# MCU_tiva.net
KiCad netlist of a schematic drawn in Altium Designer
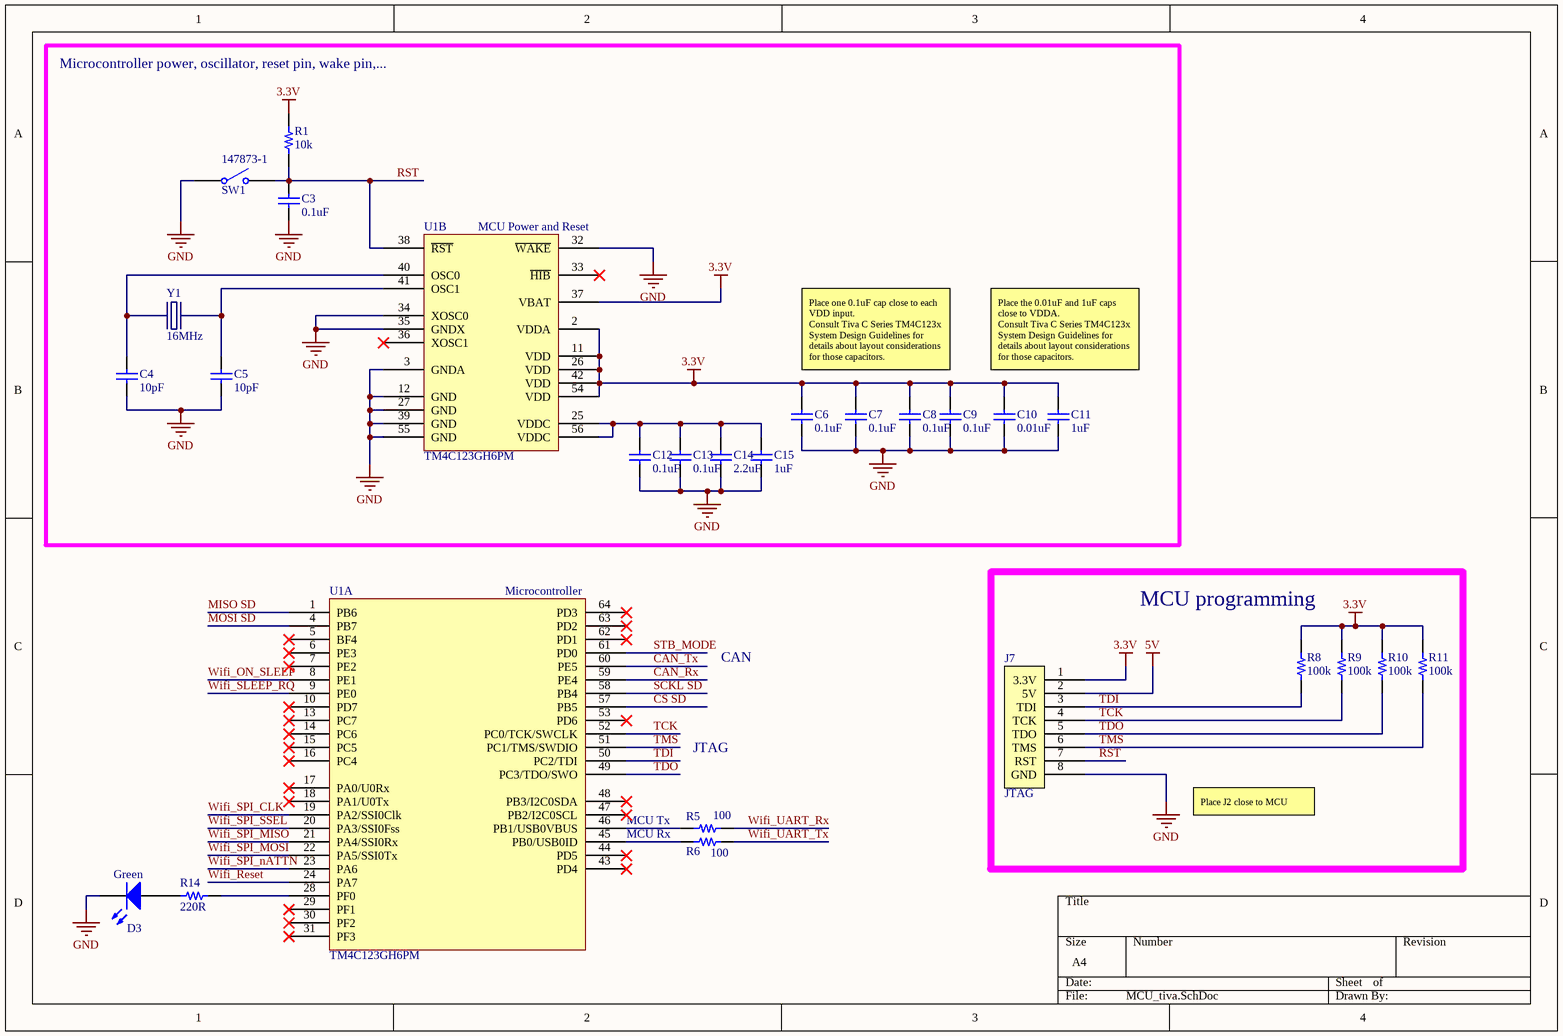
[diagram p0: MCU_tiva.SchDoc]

(export (version "E")
  (design (tool "Eeschema 10.0.6"))
  (components
    (comp (ref "C3")
      (value "0.1uF")
      (footprint "Capacitors:C0603")
      (description "0.1uF ceramic capacitor")
      (fields (field (name "MANUFACTURER") "TDK Corporation") (field (name "TOLERANCE") "10%"))
      (libsource (lib "Capacitors") (part "CAP CER 0603 0.1uF 50V C0G 10%"))
    )
    (comp (ref "C4")
      (value "10pF")
      (footprint "Capacitors:C0603")
      (description "10pF ceramic capacitor")
      (fields (field (name "MANUFACTURER") "TDK Corporation") (field (name "TOLERANCE") "5%"))
      (libsource (lib "Capacitors") (part "CAP CER 0603 10pF 50V C0G 5%"))
    )
    (comp (ref "C5")
      (value "10pF")
      (footprint "Capacitors:C0603")
      (description "10pF ceramic capacitor")
      (fields (field (name "MANUFACTURER") "TDK Corporation") (field (name "TOLERANCE") "5%"))
      (libsource (lib "Capacitors") (part "CAP CER 0603 10pF 50V C0G 5%"))
    )
    (comp (ref "C6")
      (value "0.1uF")
      (footprint "Capacitors:C0603")
      (description "0.1uF ceramic capacitor")
      (fields (field (name "MANUFACTURER") "TDK Corporation") (field (name "TOLERANCE") "10%"))
      (libsource (lib "Capacitors") (part "CAP CER 0603 0.1uF 50V C0G 10%"))
    )
    (comp (ref "C7")
      (value "0.1uF")
      (footprint "Capacitors:C0603")
      (description "0.1uF ceramic capacitor")
      (fields (field (name "MANUFACTURER") "TDK Corporation") (field (name "TOLERANCE") "10%"))
      (libsource (lib "Capacitors") (part "CAP CER 0603 0.1uF 50V C0G 10%"))
    )
    (comp (ref "C8")
      (value "0.1uF")
      (footprint "Capacitors:C0603")
      (description "0.1uF ceramic capacitor")
      (fields (field (name "MANUFACTURER") "TDK Corporation") (field (name "TOLERANCE") "10%"))
      (libsource (lib "Capacitors") (part "CAP CER 0603 0.1uF 50V C0G 10%"))
    )
    (comp (ref "C9")
      (value "0.1uF")
      (footprint "Capacitors:C0603")
      (description "0.1uF ceramic capacitor")
      (fields (field (name "MANUFACTURER") "TDK Corporation") (field (name "TOLERANCE") "10%"))
      (libsource (lib "Capacitors") (part "CAP CER 0603 0.1uF 50V C0G 10%"))
    )
    (comp (ref "C10")
      (value "0.01uF")
      (footprint "Capacitors:C0603")
      (description "0.01uF ceramic capacitor")
      (fields (field (name "MANUFACTURER") "TDK Corporation") (field (name "TOLERANCE") "10%"))
      (libsource (lib "Capacitors") (part "CAP CER 0603 0.01uF 50V X7R 10%"))
    )
    (comp (ref "C11")
      (value "1uF")
      (footprint "Capacitors:C0603")
      (description "1uF ceramic capacitor")
      (fields (field (name "MANUFACTURER") "TDK Corporation") (field (name "TOLERANCE") "20%"))
      (libsource (lib "Capacitors") (part "CAP CER 0603 1uF 25V X7R 20%"))
    )
    (comp (ref "C12")
      (value "0.1uF")
      (footprint "Capacitors:C0603")
      (description "0.1uF ceramic capacitor")
      (fields (field (name "MANUFACTURER") "TDK Corporation") (field (name "TOLERANCE") "10%"))
      (libsource (lib "Capacitors") (part "CAP CER 0603 0.1uF 50V C0G 10%"))
    )
    (comp (ref "C13")
      (value "0.1uF")
      (footprint "Capacitors:C0603")
      (description "0.1uF ceramic capacitor")
      (fields (field (name "MANUFACTURER") "TDK Corporation") (field (name "TOLERANCE") "10%"))
      (libsource (lib "Capacitors") (part "CAP CER 0603 0.1uF 50V C0G 10%"))
    )
    (comp (ref "C14")
      (value "2.2uF")
      (footprint "Capacitors:C0603")
      (description "2.2uF ceramic capacitor")
      (fields (field (name "MANUFACTURER") "TDK Corporation") (field (name "TOLERANCE") "10%"))
      (libsource (lib "Capacitors") (part "CAP CER 0603 2.2uF 6.3V X7R 10%"))
    )
    (comp (ref "C15")
      (value "1uF")
      (footprint "Capacitors:C0603")
      (description "1uF ceramic capacitor")
      (fields (field (name "MANUFACTURER") "TDK Corporation") (field (name "TOLERANCE") "20%"))
      (libsource (lib "Capacitors") (part "CAP CER 0603 1uF 25V X7R 20%"))
    )
    (comp (ref "D3")
      (value "Green")
      (footprint "Diodes:LED1206")
      (description "Green LED 1206")
      (fields (field (name "PART_NUMBER") "LTST-C150KGKT") (field (name "MANUFACTURER") "Liteon"))
      (libsource (lib "Diodes") (part "LTST-C150KGKT"))
    )
    (comp (ref "J7")
      (value "JTAG")
      (footprint "Connectors:JTAG_Header")
      (description "JTAG header, MCU programming")
      (libsource (lib "Connectors") (part "JTAG_Header"))
    )
    (comp (ref "R1")
      (value "10k")
      (footprint "Resistors:R0603")
      (description "10 kOhms resistor")
      (fields (field (name "PART_NUMBER") "CRCW060310K0JNEA") (field (name "MANUFACTURER") "Vishay"))
      (libsource (lib "Resistors") (part "RES 0603 10k 5% 0.1W"))
    )
    (comp (ref "R5")
      (value "100")
      (footprint "Resistors:R0603")
      (description "100 Ohms resistor, 1/4W")
      (fields (field (name "PART_NUMBER") "ESR03EZPJ101") (field (name "MANUFACTURER") "Rohm Semiconductor"))
      (libsource (lib "Resistors") (part "RES 0603 100R 5% 1/4W"))
    )
    (comp (ref "R6")
      (value "100")
      (footprint "Resistors:R0603")
      (description "100 Ohms resistor, 1/4W")
      (fields (field (name "PART_NUMBER") "ESR03EZPJ101") (field (name "MANUFACTURER") "Rohm Semiconductor"))
      (libsource (lib "Resistors") (part "RES 0603 100R 5% 1/4W"))
    )
    (comp (ref "R8")
      (value "100k")
      (footprint "Resistors:R0603")
      (description "100 kOhm resistor")
      (fields (field (name "PART_NUMBER") "CRCW0603100KJNEA") (field (name "MANUFACTURER") "Vishay"))
      (libsource (lib "Resistors") (part "RES 0603 100k 5% 0.1W"))
    )
    (comp (ref "R9")
      (value "100k")
      (footprint "Resistors:R0603")
      (description "100 kOhm resistor")
      (fields (field (name "PART_NUMBER") "CRCW0603100KJNEA") (field (name "MANUFACTURER") "Vishay"))
      (libsource (lib "Resistors") (part "RES 0603 100k 5% 0.1W"))
    )
    (comp (ref "R10")
      (value "100k")
      (footprint "Resistors:R0603")
      (description "100 kOhm resistor")
      (fields (field (name "PART_NUMBER") "CRCW0603100KJNEA") (field (name "MANUFACTURER") "Vishay"))
      (libsource (lib "Resistors") (part "RES 0603 100k 5% 0.1W"))
    )
    (comp (ref "R11")
      (value "100k")
      (footprint "Resistors:R0603")
      (description "100 kOhm resistor")
      (fields (field (name "PART_NUMBER") "CRCW0603100KJNEA") (field (name "MANUFACTURER") "Vishay"))
      (libsource (lib "Resistors") (part "RES 0603 100k 5% 0.1W"))
    )
    (comp (ref "R14")
      (value "220R")
      (footprint "Resistors:R0603")
      (description "220 Ohms resistor, 1/4W")
      (fields (field (name "PART_NUMBER") "ESR03EZPJ221") (field (name "MANUFACTURER") "Rohm Semiconductor"))
      (libsource (lib "Resistors") (part "RES 0603 220R 5% 1/4W"))
    )
    (comp (ref "SW1")
      (value "147873-1")
      (footprint "Other:147873")
      (description "Pushbutton switch SPST, 2 pins")
      (fields (field (name "MANUFACTURER") "TE Connectivity"))
      (libsource (lib "Other") (part "147873-1"))
    )
    (comp (ref "U1")
      (value "Microcontroller")
      (footprint "IC:LQFP64")
      (description "32 bit Microcontroller")
      (fields (field (name "MANUFACTURER") "Texas Instrument") (field (name "PART_NUMBER") "TM4C123GH6PM"))
      (libsource (lib "IC") (part "TM4C123GN6PM"))
    )
    (comp (ref "Y1")
      (value "16MHz")
      (footprint "NX5032GA")
      (description "Crystal Oscillator 16 MHz")
      (fields (field (name "MANUFACTURER") "NDK") (field (name "PART_NUMBER") "NX5032GA-16.000M-LN-CD-1"))
      (libsource (lib "Other") (part "NX5043GA-16.00MHz"))
    )
  )
  (nets
    (net (code "1") (name "/CAN_Rx") (class "Default")
      (node (ref "U1") (pin "59") (pinfunction "PE4_59") (pintype "passive"))
    )
    (net (code "2") (name "/CAN_Tx") (class "Default")
      (node (ref "U1") (pin "60") (pinfunction "PE5_60") (pintype "passive"))
    )
    (net (code "3") (name "/CS SD") (class "Default")
      (node (ref "U1") (pin "57") (pinfunction "PB5_57") (pintype "passive"))
    )
    (net (code "4") (name "/MISO SD") (class "Default")
      (node (ref "U1") (pin "1") (pinfunction "PB6_1") (pintype "passive"))
    )
    (net (code "5") (name "/MOSI SD") (class "Default")
      (node (ref "U1") (pin "4") (pinfunction "PB7_4") (pintype "passive"))
    )
    (net (code "6") (name "/RST") (class "Default")
      (node (ref "C3") (pin "2") (pinfunction "2_2") (pintype "passive"))
      (node (ref "J7") (pin "7") (pinfunction "RST_7") (pintype "passive"))
      (node (ref "R1") (pin "1") (pinfunction "1_1") (pintype "passive"))
      (node (ref "SW1") (pin "2") (pinfunction "NO_2") (pintype "passive"))
      (node (ref "U1") (pin "38") (pinfunction "~{RST}_38") (pintype "passive"))
    )
    (net (code "7") (name "/SCKL SD") (class "Default")
      (node (ref "U1") (pin "58") (pinfunction "PB4_58") (pintype "passive"))
    )
    (net (code "8") (name "/STB_MODE") (class "Default")
      (node (ref "U1") (pin "61") (pinfunction "PD0_61") (pintype "passive"))
    )
    (net (code "9") (name "/TCK") (class "Default")
      (node (ref "J7") (pin "4") (pinfunction "TCK_4") (pintype "passive"))
      (node (ref "R9") (pin "1") (pinfunction "1_1") (pintype "passive"))
      (node (ref "U1") (pin "52") (pinfunction "PC0/TCK/SWCLK_52") (pintype "passive"))
    )
    (net (code "10") (name "/TDI") (class "Default")
      (node (ref "J7") (pin "3") (pinfunction "TDI_3") (pintype "passive"))
      (node (ref "R8") (pin "1") (pinfunction "1_1") (pintype "passive"))
      (node (ref "U1") (pin "50") (pinfunction "PC2/TDI_50") (pintype "passive"))
    )
    (net (code "11") (name "/TDO") (class "Default")
      (node (ref "J7") (pin "5") (pinfunction "TDO_5") (pintype "passive"))
      (node (ref "R10") (pin "1") (pinfunction "1_1") (pintype "passive"))
      (node (ref "U1") (pin "49") (pinfunction "PC3/TDO/SWO_49") (pintype "passive"))
    )
    (net (code "12") (name "/TMS") (class "Default")
      (node (ref "J7") (pin "6") (pinfunction "TMS_6") (pintype "passive"))
      (node (ref "R11") (pin "1") (pinfunction "1_1") (pintype "passive"))
      (node (ref "U1") (pin "51") (pinfunction "PC1/TMS/SWDIO_51") (pintype "passive"))
    )
    (net (code "13") (name "/Wifi_ON_SLEEP") (class "Default")
      (node (ref "U1") (pin "8") (pinfunction "PE1_8") (pintype "passive"))
    )
    (net (code "14") (name "/Wifi_Reset") (class "Default")
      (node (ref "U1") (pin "24") (pinfunction "PA7_24") (pintype "passive"))
    )
    (net (code "15") (name "/Wifi_SLEEP_RQ") (class "Default")
      (node (ref "U1") (pin "9") (pinfunction "PE0_9") (pintype "passive"))
    )
    (net (code "16") (name "/Wifi_SPI_CLK") (class "Default")
      (node (ref "U1") (pin "19") (pinfunction "PA2/SSI0Clk_19") (pintype "passive"))
    )
    (net (code "17") (name "/Wifi_SPI_MISO") (class "Default")
      (node (ref "U1") (pin "21") (pinfunction "PA4/SSI0Rx_21") (pintype "passive"))
    )
    (net (code "18") (name "/Wifi_SPI_MOSI") (class "Default")
      (node (ref "U1") (pin "22") (pinfunction "PA5/SSI0Tx_22") (pintype "passive"))
    )
    (net (code "19") (name "/Wifi_SPI_SSEL") (class "Default")
      (node (ref "U1") (pin "20") (pinfunction "PA3/SSI0Fss_20") (pintype "passive"))
    )
    (net (code "20") (name "/Wifi_SPI_nATTN") (class "Default")
      (node (ref "U1") (pin "23") (pinfunction "PA6_23") (pintype "passive"))
    )
    (net (code "21") (name "/Wifi_UART_Rx") (class "Default")
      (node (ref "R5") (pin "1") (pinfunction "1_1") (pintype "passive"))
    )
    (net (code "22") (name "/Wifi_UART_Tx") (class "Default")
      (node (ref "R6") (pin "1") (pinfunction "1_1") (pintype "passive"))
    )
    (net (code "23") (name "3.3V") (class "Default")
      (node (ref "C10") (pin "2") (pinfunction "2_2") (pintype "passive"))
      (node (ref "C11") (pin "2") (pinfunction "2_2") (pintype "passive"))
      (node (ref "C6") (pin "2") (pinfunction "2_2") (pintype "passive"))
      (node (ref "C7") (pin "2") (pinfunction "2_2") (pintype "passive"))
      (node (ref "C8") (pin "2") (pinfunction "2_2") (pintype "passive"))
      (node (ref "C9") (pin "2") (pinfunction "2_2") (pintype "passive"))
      (node (ref "J7") (pin "1") (pinfunction "3.3V_1") (pintype "passive"))
      (node (ref "R1") (pin "2") (pinfunction "2_2") (pintype "passive"))
      (node (ref "R10") (pin "2") (pinfunction "2_2") (pintype "passive"))
      (node (ref "R11") (pin "2") (pinfunction "2_2") (pintype "passive"))
      (node (ref "R8") (pin "2") (pinfunction "2_2") (pintype "passive"))
      (node (ref "R9") (pin "2") (pinfunction "2_2") (pintype "passive"))
      (node (ref "U1") (pin "11") (pinfunction "VDD_11") (pintype "passive"))
      (node (ref "U1") (pin "2") (pinfunction "VDDA_2") (pintype "passive"))
      (node (ref "U1") (pin "26") (pinfunction "VDD_26") (pintype "passive"))
      (node (ref "U1") (pin "37") (pinfunction "VBAT_37") (pintype "passive"))
      (node (ref "U1") (pin "42") (pinfunction "VDD_42") (pintype "passive"))
      (node (ref "U1") (pin "54") (pinfunction "VDD_54") (pintype "passive"))
    )
    (net (code "24") (name "5V") (class "Default")
      (node (ref "J7") (pin "2") (pinfunction "5V_2") (pintype "passive"))
    )
    (net (code "25") (name "GND") (class "Default")
      (node (ref "C10") (pin "1") (pinfunction "1_1") (pintype "passive"))
      (node (ref "C11") (pin "1") (pinfunction "1_1") (pintype "passive"))
      (node (ref "C12") (pin "1") (pinfunction "1_1") (pintype "passive"))
      (node (ref "C13") (pin "1") (pinfunction "1_1") (pintype "passive"))
      (node (ref "C14") (pin "1") (pinfunction "1_1") (pintype "passive"))
      (node (ref "C15") (pin "1") (pinfunction "1_1") (pintype "passive"))
      (node (ref "C3") (pin "1") (pinfunction "1_1") (pintype "passive"))
      (node (ref "C4") (pin "1") (pinfunction "1_1") (pintype "passive"))
      (node (ref "C5") (pin "1") (pinfunction "1_1") (pintype "passive"))
      (node (ref "C6") (pin "1") (pinfunction "1_1") (pintype "passive"))
      (node (ref "C7") (pin "1") (pinfunction "1_1") (pintype "passive"))
      (node (ref "C8") (pin "1") (pinfunction "1_1") (pintype "passive"))
      (node (ref "C9") (pin "1") (pinfunction "1_1") (pintype "passive"))
      (node (ref "D3") (pin "2") (pinfunction "K_2") (pintype "passive"))
      (node (ref "J7") (pin "8") (pinfunction "GND_8") (pintype "passive"))
      (node (ref "SW1") (pin "1") (pinfunction "COMMON_1") (pintype "passive"))
      (node (ref "U1") (pin "12") (pinfunction "GND_12") (pintype "passive"))
      (node (ref "U1") (pin "27") (pinfunction "GND_27") (pintype "passive"))
      (node (ref "U1") (pin "3") (pinfunction "GNDA_3") (pintype "passive"))
      (node (ref "U1") (pin "32") (pinfunction "~{WAKE}_32") (pintype "passive"))
      (node (ref "U1") (pin "34") (pinfunction "XOSC0_34") (pintype "passive"))
      (node (ref "U1") (pin "35") (pinfunction "GNDX_35") (pintype "passive"))
      (node (ref "U1") (pin "39") (pinfunction "GND_39") (pintype "passive"))
      (node (ref "U1") (pin "55") (pinfunction "GND_55") (pintype "passive"))
    )
    (net (code "26") (name "Net-(C12-Pad2)") (class "Default")
      (node (ref "C12") (pin "2") (pinfunction "2_2") (pintype "passive"))
      (node (ref "C13") (pin "2") (pinfunction "2_2") (pintype "passive"))
      (node (ref "C14") (pin "2") (pinfunction "2_2") (pintype "passive"))
      (node (ref "C15") (pin "2") (pinfunction "2_2") (pintype "passive"))
      (node (ref "U1") (pin "25") (pinfunction "VDDC_25") (pintype "passive"))
      (node (ref "U1") (pin "56") (pinfunction "VDDC_56") (pintype "passive"))
    )
    (net (code "27") (name "Net-(D3-A)") (class "Default")
      (node (ref "D3") (pin "1") (pinfunction "A_1") (pintype "passive"))
      (node (ref "R14") (pin "1") (pinfunction "1_1") (pintype "passive"))
    )
    (net (code "28") (name "Net-(U1A-PB0{slash}USB0ID)") (class "Default")
      (node (ref "R6") (pin "2") (pinfunction "2_2") (pintype "passive"))
      (node (ref "U1") (pin "45") (pinfunction "PB0/USB0ID_45") (pintype "passive"))
    )
    (net (code "29") (name "Net-(U1A-PB1{slash}USB0VBUS)") (class "Default")
      (node (ref "R5") (pin "2") (pinfunction "2_2") (pintype "passive"))
      (node (ref "U1") (pin "46") (pinfunction "PB1/USB0VBUS_46") (pintype "passive"))
    )
    (net (code "30") (name "Net-(U1A-PF0)") (class "Default")
      (node (ref "R14") (pin "2") (pinfunction "2_2") (pintype "passive"))
      (node (ref "U1") (pin "28") (pinfunction "PF0_28") (pintype "passive"))
    )
    (net (code "31") (name "Net-(U1B-OSC0)") (class "Default")
      (node (ref "C4") (pin "2") (pinfunction "2_2") (pintype "passive"))
      (node (ref "U1") (pin "40") (pinfunction "OSC0_40") (pintype "passive"))
      (node (ref "Y1") (pin "1") (pinfunction "1_1") (pintype "passive"))
    )
    (net (code "32") (name "Net-(U1B-OSC1)") (class "Default")
      (node (ref "C5") (pin "2") (pinfunction "2_2") (pintype "passive"))
      (node (ref "U1") (pin "41") (pinfunction "OSC1_41") (pintype "passive"))
      (node (ref "Y1") (pin "2") (pinfunction "2_2") (pintype "passive"))
    )
    (net (code "33") (name "unconnected-(U1A-BF4-Pad5)") (class "Default")
      (node (ref "U1") (pin "5") (pinfunction "BF4_5") (pintype "passive+no_connect"))
    )
    (net (code "34") (name "unconnected-(U1A-PA0{slash}U0Rx-Pad17)") (class "Default")
      (node (ref "U1") (pin "17") (pinfunction "PA0/U0Rx_17") (pintype "passive+no_connect"))
    )
    (net (code "35") (name "unconnected-(U1A-PA1{slash}U0Tx-Pad18)") (class "Default")
      (node (ref "U1") (pin "18") (pinfunction "PA1/U0Tx_18") (pintype "passive+no_connect"))
    )
    (net (code "36") (name "unconnected-(U1A-PB2{slash}I2C0SCL-Pad47)") (class "Default")
      (node (ref "U1") (pin "47") (pinfunction "PB2/I2C0SCL_47") (pintype "passive+no_connect"))
    )
    (net (code "37") (name "unconnected-(U1A-PB3{slash}I2C0SDA-Pad48)") (class "Default")
      (node (ref "U1") (pin "48") (pinfunction "PB3/I2C0SDA_48") (pintype "passive+no_connect"))
    )
    (net (code "38") (name "unconnected-(U1A-PC4-Pad16)") (class "Default")
      (node (ref "U1") (pin "16") (pinfunction "PC4_16") (pintype "passive+no_connect"))
    )
    (net (code "39") (name "unconnected-(U1A-PC5-Pad15)") (class "Default")
      (node (ref "U1") (pin "15") (pinfunction "PC5_15") (pintype "passive+no_connect"))
    )
    (net (code "40") (name "unconnected-(U1A-PC6-Pad14)") (class "Default")
      (node (ref "U1") (pin "14") (pinfunction "PC6_14") (pintype "passive+no_connect"))
    )
    (net (code "41") (name "unconnected-(U1A-PC7-Pad13)") (class "Default")
      (node (ref "U1") (pin "13") (pinfunction "PC7_13") (pintype "passive+no_connect"))
    )
    (net (code "42") (name "unconnected-(U1A-PD1-Pad62)") (class "Default")
      (node (ref "U1") (pin "62") (pinfunction "PD1_62") (pintype "passive+no_connect"))
    )
    (net (code "43") (name "unconnected-(U1A-PD2-Pad63)") (class "Default")
      (node (ref "U1") (pin "63") (pinfunction "PD2_63") (pintype "passive+no_connect"))
    )
    (net (code "44") (name "unconnected-(U1A-PD3-Pad64)") (class "Default")
      (node (ref "U1") (pin "64") (pinfunction "PD3_64") (pintype "passive+no_connect"))
    )
    (net (code "45") (name "unconnected-(U1A-PD4-Pad43)") (class "Default")
      (node (ref "U1") (pin "43") (pinfunction "PD4_43") (pintype "passive+no_connect"))
    )
    (net (code "46") (name "unconnected-(U1A-PD5-Pad44)") (class "Default")
      (node (ref "U1") (pin "44") (pinfunction "PD5_44") (pintype "passive+no_connect"))
    )
    (net (code "47") (name "unconnected-(U1A-PD6-Pad53)") (class "Default")
      (node (ref "U1") (pin "53") (pinfunction "PD6_53") (pintype "passive+no_connect"))
    )
    (net (code "48") (name "unconnected-(U1A-PD7-Pad10)") (class "Default")
      (node (ref "U1") (pin "10") (pinfunction "PD7_10") (pintype "passive+no_connect"))
    )
    (net (code "49") (name "unconnected-(U1A-PE2-Pad7)") (class "Default")
      (node (ref "U1") (pin "7") (pinfunction "PE2_7") (pintype "passive+no_connect"))
    )
    (net (code "50") (name "unconnected-(U1A-PE3-Pad6)") (class "Default")
      (node (ref "U1") (pin "6") (pinfunction "PE3_6") (pintype "passive+no_connect"))
    )
    (net (code "51") (name "unconnected-(U1A-PF1-Pad29)") (class "Default")
      (node (ref "U1") (pin "29") (pinfunction "PF1_29") (pintype "passive+no_connect"))
    )
    (net (code "52") (name "unconnected-(U1A-PF2-Pad30)") (class "Default")
      (node (ref "U1") (pin "30") (pinfunction "PF2_30") (pintype "passive+no_connect"))
    )
    (net (code "53") (name "unconnected-(U1A-PF3-Pad31)") (class "Default")
      (node (ref "U1") (pin "31") (pinfunction "PF3_31") (pintype "passive+no_connect"))
    )
    (net (code "54") (name "unconnected-(U1B-XOSC1-Pad36)") (class "Default")
      (node (ref "U1") (pin "36") (pinfunction "XOSC1_36") (pintype "passive+no_connect"))
    )
    (net (code "55") (name "unconnected-(U1B-~{HIB}-Pad33)") (class "Default")
      (node (ref "U1") (pin "33") (pinfunction "~{HIB}_33") (pintype "passive+no_connect"))
    )
  )
)
